# IoT_Greenhouse_V1_0_A_-_Inputs.net
KiCad netlist of a schematic drawn in Altium Designer
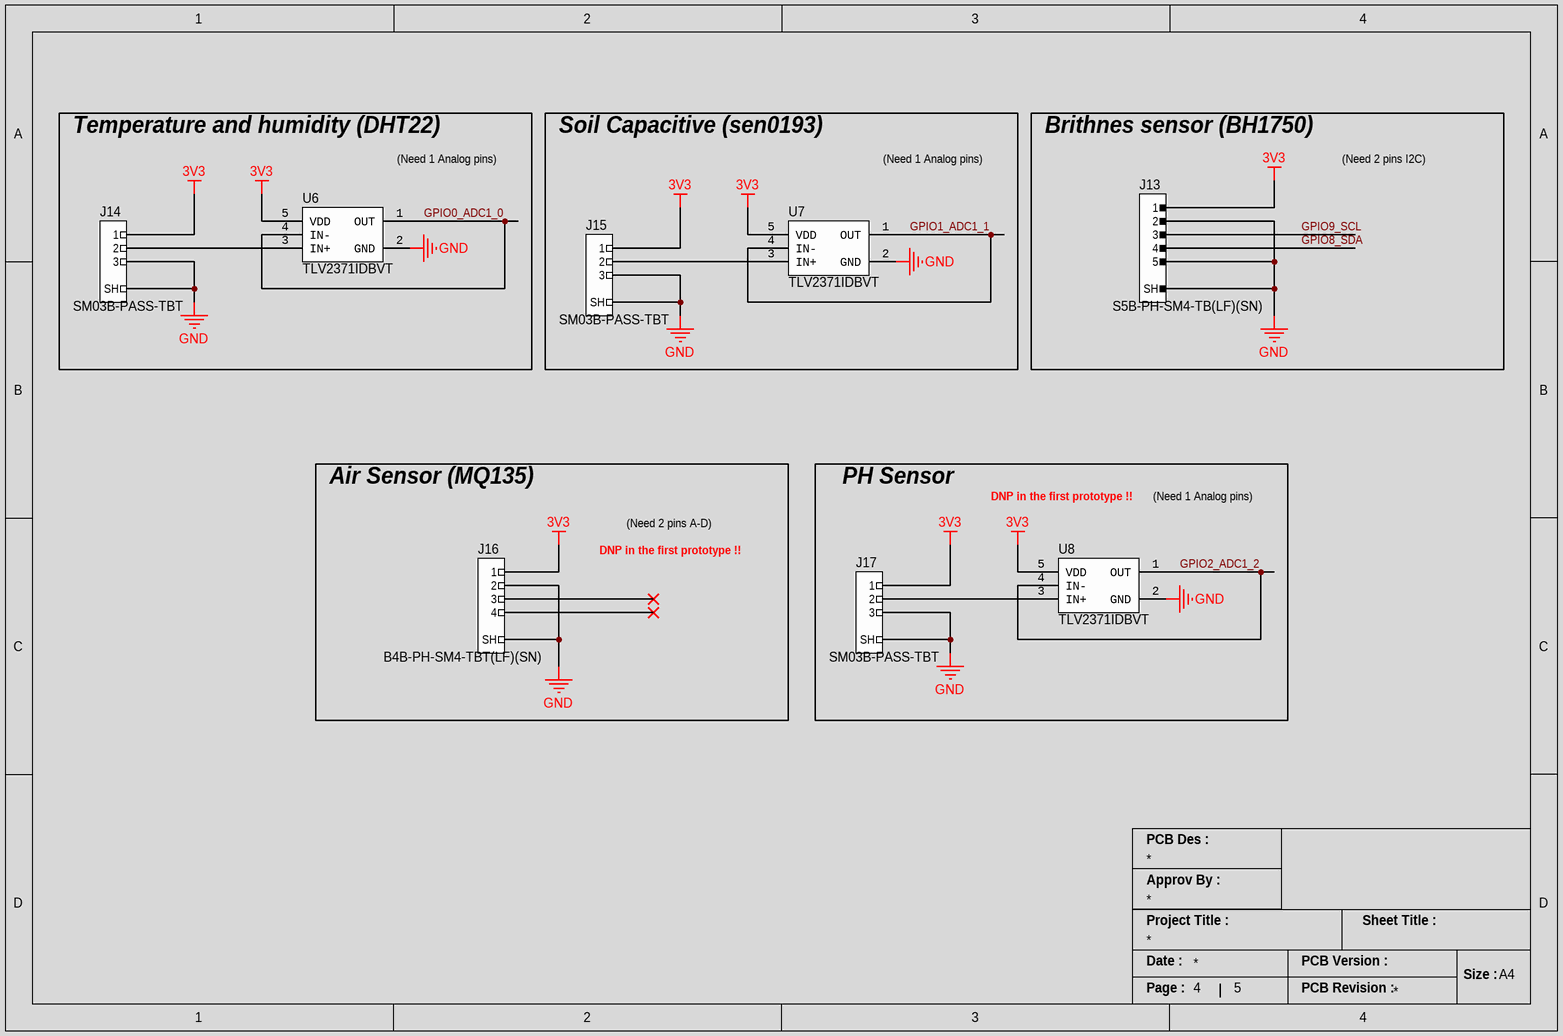
[diagram p0: IoT_Greenhouse V1.0 A - Inputs.SchDoc]

(export (version "E")
  (design (tool "Eeschema 10.0.6"))
  (components
    (comp (ref "J13")
      (value "S5B-PH-SM4-TB(LF)(SN)")
      (footprint "CONN_JST_S5B-PH-SM4-TB_LF_SN_0")
      (description "Conn Shrouded Header (4 Sides) HDR 5 POS 2mm Solder RA SMD T/R")
      (fields (field (name "MANUFACTURER") "JST"))
      (libsource (lib "Electronic Devices_LIB") (part "CONN_JST_PH_RA_5P_2mm"))
    )
    (comp (ref "J14")
      (value "SM03B-PASS-TBT")
      (footprint "CONN_JST_SM03B-PASS-TBT_LF_SN_MFG")
      (description "Conn Header SMD R/a 3POS 2MM")
      (fields (field (name "MANUFACTURER") "JST"))
      (libsource (lib "Electronic Devices_LIB") (part "CONN_JST_PH_3P_2MM_SM03B-PASS-TBT"))
    )
    (comp (ref "J15")
      (value "SM03B-PASS-TBT")
      (footprint "CONN_JST_SM03B-PASS-TBT_LF_SN_MFG")
      (description "Conn Header SMD R/a 3POS 2MM")
      (fields (field (name "MANUFACTURER") "JST"))
      (libsource (lib "Electronic Devices_LIB") (part "CONN_JST_PH_3P_2MM_SM03B-PASS-TBT"))
    )
    (comp (ref "J16")
      (value "B4B-PH-SM4-TBT(LF)(SN)")
      (footprint "CONN_JST_0_MFG_4P")
      (fields (field (name "MANUFACTURER") "JST") (field (name "JLCPCB PART NUMBER") "C265116"))
      (libsource (lib "Electronic Devices_LIB") (part "CONN_JST_PH_4P_2mm_JLCPCB"))
    )
    (comp (ref "J17")
      (value "SM03B-PASS-TBT")
      (footprint "CONN_JST_SM03B-PASS-TBT_LF_SN_MFG")
      (description "Conn Header SMD R/a 3POS 2MM")
      (fields (field (name "MANUFACTURER") "JST"))
      (libsource (lib "Electronic Devices_LIB") (part "CONN_JST_PH_3P_2MM_SM03B-PASS-TBT"))
    )
    (comp (ref "U6")
      (value "TLV2371IDBVT")
      (footprint "IC_AMP_OP_SOT95P280X145-5N")
      (description "Single 550-uA/channel, 3MHz, RRIO op amp 5-SOT-23 -40 to 125")
      (fields (field (name "MANUFACTURER") "Texas Instruments"))
      (libsource (lib "Electronic Devices_LIB") (part "IC_AMP_OP_TLV2371IDBVT"))
    )
    (comp (ref "U7")
      (value "TLV2371IDBVT")
      (footprint "IC_AMP_OP_SOT95P280X145-5N")
      (description "Single 550-uA/channel, 3MHz, RRIO op amp 5-SOT-23 -40 to 125")
      (fields (field (name "MANUFACTURER") "Texas Instruments"))
      (libsource (lib "Electronic Devices_LIB") (part "IC_AMP_OP_TLV2371IDBVT"))
    )
    (comp (ref "U8")
      (value "TLV2371IDBVT")
      (footprint "IC_AMP_OP_SOT95P280X145-5N")
      (description "Single 550-uA/channel, 3MHz, RRIO op amp 5-SOT-23 -40 to 125")
      (fields (field (name "MANUFACTURER") "Texas Instruments"))
      (libsource (lib "Electronic Devices_LIB") (part "IC_AMP_OP_TLV2371IDBVT"))
    )
  )
  (nets
    (net (code "1") (name "/GPIO0_ADC1_0") (class "Default")
      (node (ref "U6") (pin "1") (pinfunction "OUT_1") (pintype "passive"))
      (node (ref "U6") (pin "4") (pinfunction "IN-_4") (pintype "passive"))
    )
    (net (code "2") (name "/GPIO1_ADC1_1") (class "Default")
      (node (ref "U7") (pin "1") (pinfunction "OUT_1") (pintype "passive"))
      (node (ref "U7") (pin "4") (pinfunction "IN-_4") (pintype "passive"))
    )
    (net (code "3") (name "/GPIO2_ADC1_2") (class "Default")
      (node (ref "U8") (pin "1") (pinfunction "OUT_1") (pintype "passive"))
      (node (ref "U8") (pin "4") (pinfunction "IN-_4") (pintype "passive"))
    )
    (net (code "4") (name "/GPIO8_SDA") (class "Default")
      (node (ref "J13") (pin "4") (pinfunction "4_4") (pintype "passive"))
    )
    (net (code "5") (name "/GPIO9_SCL") (class "Default")
      (node (ref "J13") (pin "3") (pinfunction "3_3") (pintype "passive"))
    )
    (net (code "6") (name "3V3") (class "Default")
      (node (ref "J13") (pin "1") (pinfunction "1_1") (pintype "passive"))
      (node (ref "J14") (pin "1") (pinfunction "1_1") (pintype "passive"))
      (node (ref "J15") (pin "1") (pinfunction "1_1") (pintype "passive"))
      (node (ref "J16") (pin "1") (pinfunction "1_1") (pintype "passive"))
      (node (ref "J17") (pin "1") (pinfunction "1_1") (pintype "passive"))
      (node (ref "U6") (pin "5") (pinfunction "VDD_5") (pintype "power_in"))
      (node (ref "U7") (pin "5") (pinfunction "VDD_5") (pintype "power_in"))
      (node (ref "U8") (pin "5") (pinfunction "VDD_5") (pintype "power_in"))
    )
    (net (code "7") (name "GND") (class "Default")
      (node (ref "J13") (pin "0") (pinfunction "SH_0") (pintype "passive"))
      (node (ref "J13") (pin "2") (pinfunction "2_2") (pintype "passive"))
      (node (ref "J13") (pin "5") (pinfunction "5_5") (pintype "passive"))
      (node (ref "J14") (pin "3") (pinfunction "3_3") (pintype "passive"))
      (node (ref "J14") (pin "SH") (pinfunction "SH_SH") (pintype "passive"))
      (node (ref "J15") (pin "3") (pinfunction "3_3") (pintype "passive"))
      (node (ref "J15") (pin "SH") (pinfunction "SH_SH") (pintype "passive"))
      (node (ref "J16") (pin "0") (pinfunction "SH_0") (pintype "passive"))
      (node (ref "J16") (pin "2") (pinfunction "2_2") (pintype "passive"))
      (node (ref "J17") (pin "3") (pinfunction "3_3") (pintype "passive"))
      (node (ref "J17") (pin "SH") (pinfunction "SH_SH") (pintype "passive"))
      (node (ref "U6") (pin "2") (pinfunction "GND_2") (pintype "power_in"))
      (node (ref "U7") (pin "2") (pinfunction "GND_2") (pintype "power_in"))
      (node (ref "U8") (pin "2") (pinfunction "GND_2") (pintype "power_in"))
    )
    (net (code "8") (name "Net-(U6-IN+)") (class "Default")
      (node (ref "J14") (pin "2") (pinfunction "2_2") (pintype "passive"))
      (node (ref "U6") (pin "3") (pinfunction "IN+_3") (pintype "passive"))
    )
    (net (code "9") (name "Net-(U7-IN+)") (class "Default")
      (node (ref "J15") (pin "2") (pinfunction "2_2") (pintype "passive"))
      (node (ref "U7") (pin "3") (pinfunction "IN+_3") (pintype "passive"))
    )
    (net (code "10") (name "Net-(U8-IN+)") (class "Default")
      (node (ref "J17") (pin "2") (pinfunction "2_2") (pintype "passive"))
      (node (ref "U8") (pin "3") (pinfunction "IN+_3") (pintype "passive"))
    )
    (net (code "11") (name "unconnected-(J16-Pad3)") (class "Default")
      (node (ref "J16") (pin "3") (pinfunction "3_3") (pintype "passive+no_connect"))
    )
    (net (code "12") (name "unconnected-(J16-Pad4)") (class "Default")
      (node (ref "J16") (pin "4") (pinfunction "4_4") (pintype "passive+no_connect"))
    )
  )
)
